# clap_switch_pcb.net
KiCad netlist of a schematic drawn in Altium Designer
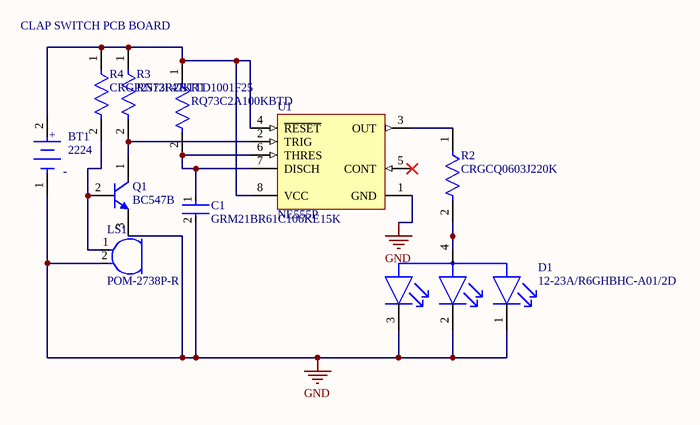
[diagram p0: clap switch pcb.SchDoc]

(export (version "E")
  (design (tool "Eeschema 10.0.6"))
  (components
    (comp (ref "BT1")
      (value "2224")
      (footprint "FP-2224-MFG")
      (description "BATTERY HOLDER C PC PIN")
      (libsource (lib "Altium Content Vault") (part "60d3b5b901a8747834971d0eb8cf3fd"))
    )
    (comp (ref "C1")
      (value "GRM21BR61C106KE15K")
      (footprint "FP-GRM21B-0_1-MFG")
      (description "Chip Multilayer Ceramic Capacitors for General Purpose, 0805, 10uF, X5R, 15%, 10%, 16V")
      (fields (field (name "TOLERANCE") "10%") (field (name "VOLTAGE") "16V"))
      (libsource (lib "Altium Content Vault") (part "b4654b650e69147ec39a6b967a45e02"))
    )
    (comp (ref "D1")
      (value "12-23A/R6GHBHC-A01/2D")
      (footprint "FP-12-23A-MFG")
      (description "LED RGB CLEAR CHIP SMD R/A")
      (fields
        (field (name "MANUFACTURER") "Everlight")
        (field (name "OCTOPART") "https://octopart.com/12-23a%2Fr6ghbhc-a01%2F2d-everlight-10561613")
      )
      (libsource (lib "Altium Content Vault") (part "0f5ba1c0a463e1debadbc8c59bbc1a5"))
    )
    (comp (ref "LS1")
      (value "POM-2738P-R")
      (footprint "FP-POM-2738P-R-MFG")
      (description "MIC COND ANALOG OMNI -38DB")
      (fields
        (field (name "MANUFACTURER") "PUI Audio, Inc.")
        (field (name "OCTOPART") "https://octopart.com/pom-2738p-r-pui+audio-19251807")
      )
      (libsource (lib "Altium Content Vault") (part "b2bcf75ddc372d3ce9fb98e3c3a2780"))
    )
    (comp (ref "Q1")
      (value "BC547B")
      (footprint "ONSC-TO-92-3-29-11")
      (description "Amplifier Transistor, NPN Silicon, 3-Pin TO-92, Bulk Box")
      (fields (field (name "MANUFACTURER") "On Semiconductor"))
      (libsource (lib "Altium Content Vault") (part "ONSC-NPN-C1B2E3-3"))
    )
    (comp (ref "R1")
      (value "RQ73C2A100KBTD")
      (footprint "FP-RQ73C2A-IPC_B")
      (description "RQ73 0805 100KΩ 0.2W 10ppm/°C 0.1% 100V")
      (libsource (lib "Altium Content Vault") (part "1029c3af85768c4190bb7ad29bc67b5"))
    )
    (comp (ref "R2")
      (value "CRGCQ0603J220K")
      (footprint "FP-CRGCQ0603-IPC_C")
      (description "CRGCQ0603 220KΩ 5% ±100ppm/°C 75V")
      (fields
        (field (name "OCTOPART") "https://octopart.com/crgcq0603j220k-te+connectivity-91018110")
        (field (name "TOLERANCE") "0.05")
      )
      (libsource (lib "Altium Content Vault") (part "1029c3af85768c4190bb7ad29bc67b5"))
    )
    (comp (ref "R3")
      (value "RN73R2BTTD1001F25")
      (footprint "FP-RN73R2B-MFG")
      (description "1kΩ ±1% 0.25W, 1/4W Chip Resistor 1206 (3216 Metric) Moisture Resistant Thin Film")
      (libsource (lib "Altium Content Vault") (part "1029c3af85768c4190bb7ad29bc67b5"))
    )
    (comp (ref "R4")
      (value "CRGP2512F47K")
      (footprint "FP-CRGP2512-IPC_C")
      (description "CRGP2512 47KΩ 2W ±100ppm/°C 1% 500V")
      (fields (field (name "TOLERANCE") "0.01"))
      (libsource (lib "Altium Content Vault") (part "1029c3af85768c4190bb7ad29bc67b5"))
    )
    (comp (ref "U1")
      (value "NE555P")
      (footprint "P0008A")
      (description "Precision Timer, 4.5 to 16 V, 0 to 70 degC, 8-Pin DIP, Pb-Free, Tube")
      (fields (field (name "MANUFACTURER") "TexasInstruments"))
      (libsource (lib "Altium Content Vault") (part "TI-NE555-P8"))
    )
  )
  (nets
    (net (code "1") (name "GND") (class "Default")
      (node (ref "BT1") (pin "1") (pinfunction "C_1") (pintype "passive"))
      (node (ref "C1") (pin "2") (pinfunction "2_2") (pintype "passive"))
      (node (ref "D1") (pin "1") (pinfunction "RED_C_1") (pintype "passive"))
      (node (ref "D1") (pin "2") (pinfunction "GREEN_C_2") (pintype "passive"))
      (node (ref "D1") (pin "3") (pinfunction "BLUE_C_3") (pintype "passive"))
      (node (ref "LS1") (pin "2") (pinfunction "C_2") (pintype "passive"))
      (node (ref "Q1") (pin "3") (pinfunction "E_3") (pintype "passive"))
      (node (ref "U1") (pin "1") (pinfunction "GND_1") (pintype "power_in"))
    )
    (net (code "2") (name "Net-(BT1-A)") (class "Default")
      (node (ref "BT1") (pin "2") (pinfunction "A_2") (pintype "passive"))
      (node (ref "R1") (pin "1") (pinfunction "1_1") (pintype "passive"))
      (node (ref "R3") (pin "1") (pinfunction "1_1") (pintype "passive"))
      (node (ref "R4") (pin "1") (pinfunction "1_1") (pintype "passive"))
      (node (ref "U1") (pin "4") (pinfunction "~{RESET}_4") (pintype "input"))
      (node (ref "U1") (pin "8") (pinfunction "VCC_8") (pintype "power_in"))
    )
    (net (code "3") (name "Net-(D1-COMMON_ANODE)") (class "Default")
      (node (ref "D1") (pin "4") (pinfunction "COMMON_ANODE_4") (pintype "passive"))
      (node (ref "R2") (pin "2") (pinfunction "2_2") (pintype "passive"))
    )
    (net (code "4") (name "Net-(LS1-A)") (class "Default")
      (node (ref "LS1") (pin "1") (pinfunction "A_1") (pintype "passive"))
      (node (ref "Q1") (pin "2") (pinfunction "B_2") (pintype "passive"))
      (node (ref "R4") (pin "2") (pinfunction "2_2") (pintype "passive"))
    )
    (net (code "5") (name "Net-(Q1-C)") (class "Default")
      (node (ref "Q1") (pin "1") (pinfunction "C_1") (pintype "passive"))
      (node (ref "R3") (pin "2") (pinfunction "2_2") (pintype "passive"))
      (node (ref "U1") (pin "2") (pinfunction "TRIG_2") (pintype "input"))
    )
    (net (code "6") (name "Net-(U1-DISCH)") (class "Default")
      (node (ref "C1") (pin "1") (pinfunction "1_1") (pintype "passive"))
      (node (ref "R1") (pin "2") (pinfunction "2_2") (pintype "passive"))
      (node (ref "U1") (pin "6") (pinfunction "THRES_6") (pintype "input"))
      (node (ref "U1") (pin "7") (pinfunction "DISCH_7") (pintype "open_collector"))
    )
    (net (code "7") (name "Net-(U1-OUT)") (class "Default")
      (node (ref "R2") (pin "1") (pinfunction "1_1") (pintype "passive"))
      (node (ref "U1") (pin "3") (pinfunction "OUT_3") (pintype "output"))
    )
    (net (code "8") (name "unconnected-(U1-CONT-Pad5)") (class "Default")
      (node (ref "U1") (pin "5") (pinfunction "CONT_5") (pintype "input+no_connect"))
    )
  )
)
